# md_ver10_1.net
KiCad netlist of a schematic drawn in EAGLE
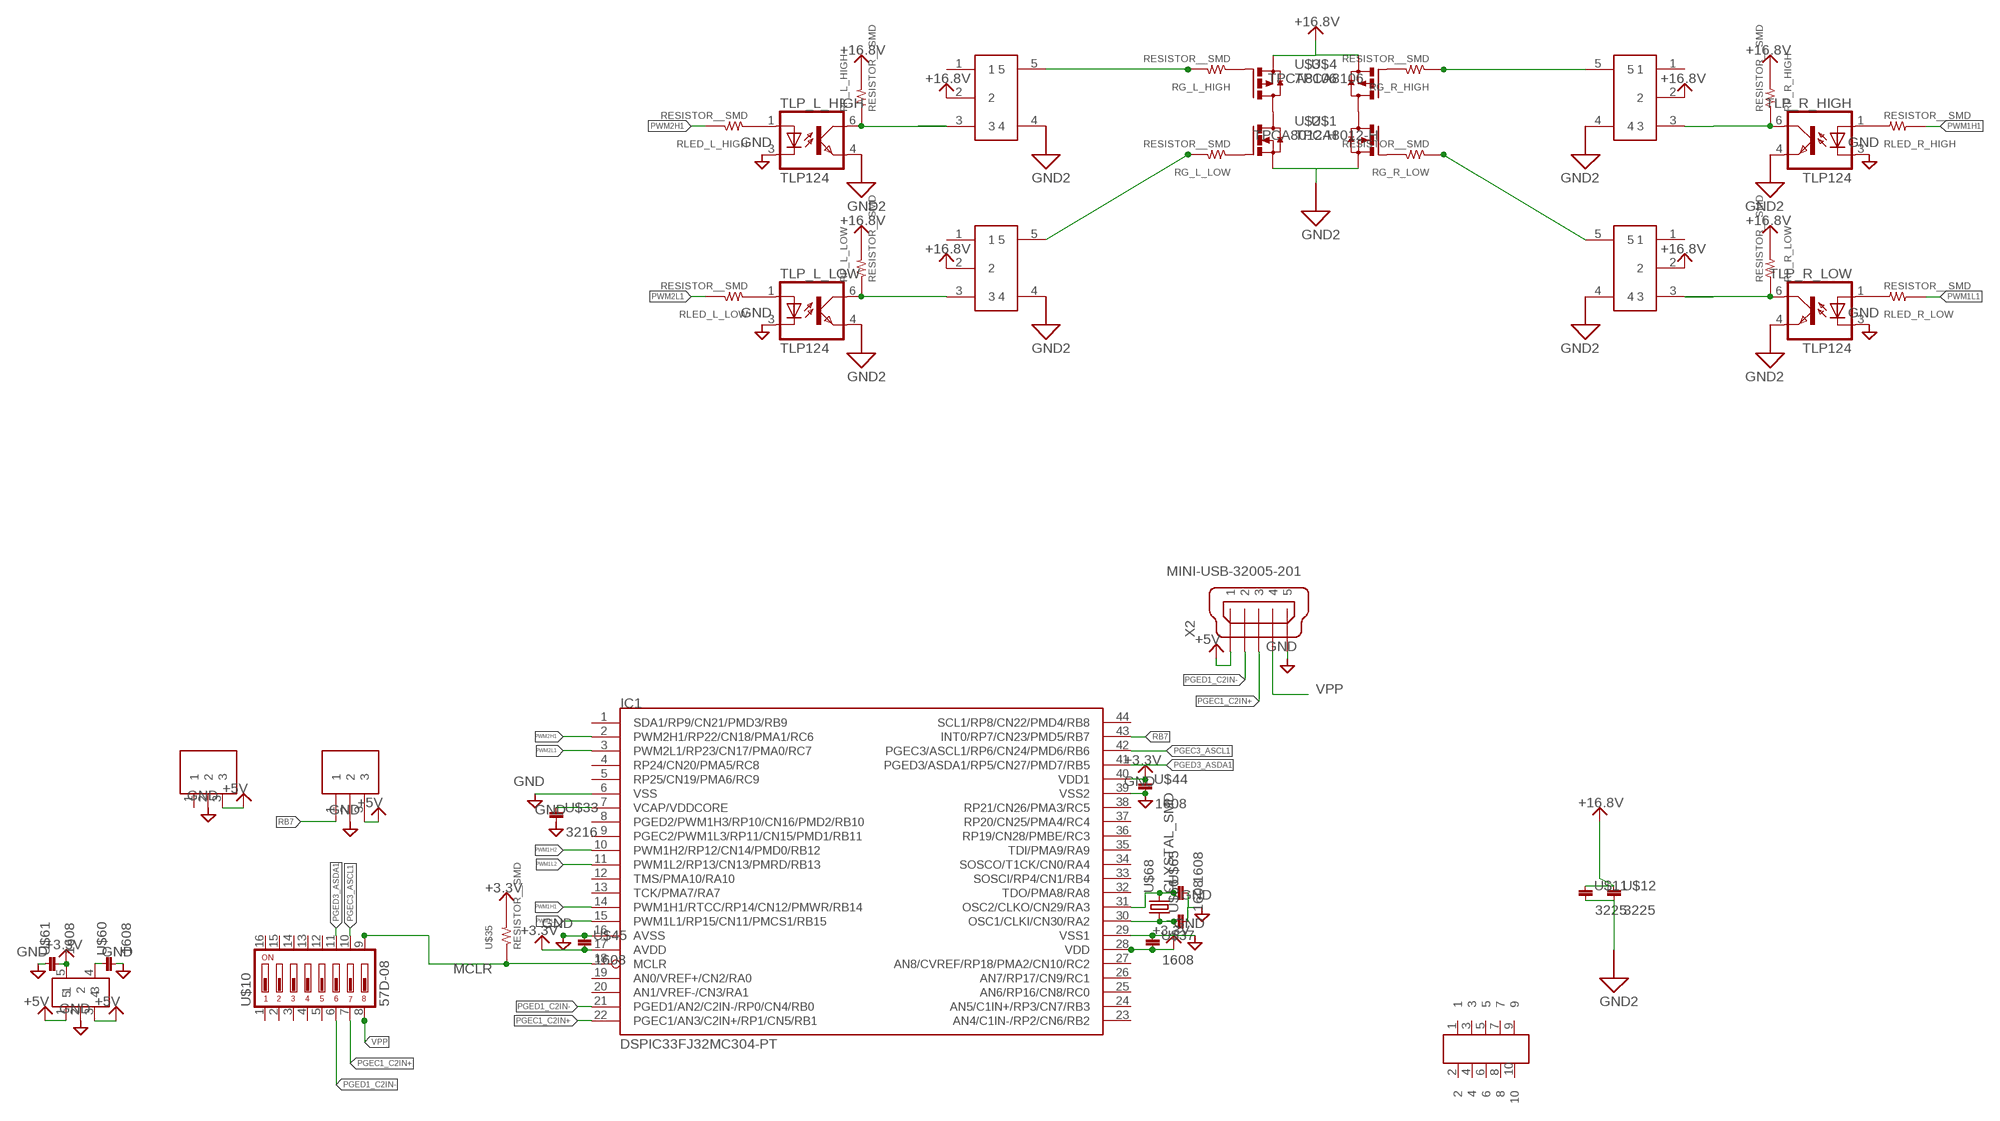
[diagram p0: schematic, sheet 1]

(export (version "E")
  (design (tool "Eeschema 10.0.6"))
  (components
    (comp (ref "IC1")
      (value "DSPIC33FJ32MC304-PT")
      (footprint "eagle-import:TQFP44")
      (libsource (lib "eagle-import") (part "DSPIC33FJ32MC304-PT"))
    )
    (comp (ref "IC_L_HIGH")
      (value "MCP1415")
      (footprint "eagle-import:SOT23-5L")
      (libsource (lib "eagle-import") (part "MCP1415"))
    )
    (comp (ref "IC_L_LOW")
      (value "MCP1415")
      (footprint "eagle-import:SOT23-5L")
      (libsource (lib "eagle-import") (part "MCP1415"))
    )
    (comp (ref "IC_R_HIGH")
      (value "MCP1415")
      (footprint "eagle-import:SOT23-5L")
      (libsource (lib "eagle-import") (part "MCP1415"))
    )
    (comp (ref "IC_R_LOW")
      (value "MCP1415")
      (footprint "eagle-import:SOT23-5L")
      (libsource (lib "eagle-import") (part "MCP1415"))
    )
    (comp (ref "RG_L_HIGH")
      (value "RESISTOR__SMD")
      (footprint "eagle-import:1608")
      (libsource (lib "eagle-import") (part "RESISTOR__SMD"))
    )
    (comp (ref "RG_L_LOW")
      (value "RESISTOR__SMD")
      (footprint "eagle-import:1608")
      (libsource (lib "eagle-import") (part "RESISTOR__SMD"))
    )
    (comp (ref "RG_R_HIGH")
      (value "RESISTOR__SMD")
      (footprint "eagle-import:1608")
      (libsource (lib "eagle-import") (part "RESISTOR__SMD"))
    )
    (comp (ref "RG_R_LOW")
      (value "RESISTOR__SMD")
      (footprint "eagle-import:1608")
      (libsource (lib "eagle-import") (part "RESISTOR__SMD"))
    )
    (comp (ref "RLED_L_HIGH")
      (value "RESISTOR__SMD")
      (footprint "eagle-import:1608")
      (libsource (lib "eagle-import") (part "RESISTOR__SMD"))
    )
    (comp (ref "RLED_L_LOW")
      (value "RESISTOR__SMD")
      (footprint "eagle-import:1608")
      (libsource (lib "eagle-import") (part "RESISTOR__SMD"))
    )
    (comp (ref "RLED_R_HIGH")
      (value "RESISTOR__SMD")
      (footprint "eagle-import:1608")
      (libsource (lib "eagle-import") (part "RESISTOR__SMD"))
    )
    (comp (ref "RLED_R_LOW")
      (value "RESISTOR__SMD")
      (footprint "eagle-import:1608")
      (libsource (lib "eagle-import") (part "RESISTOR__SMD"))
    )
    (comp (ref "RP_L_HIGH")
      (value "RESISTOR__SMD")
      (footprint "eagle-import:1608")
      (libsource (lib "eagle-import") (part "RESISTOR__SMD"))
    )
    (comp (ref "RP_L_LOW")
      (value "RESISTOR__SMD")
      (footprint "eagle-import:1608")
      (libsource (lib "eagle-import") (part "RESISTOR__SMD"))
    )
    (comp (ref "RP_R_HIGH")
      (value "RESISTOR__SMD")
      (footprint "eagle-import:1608")
      (libsource (lib "eagle-import") (part "RESISTOR__SMD"))
    )
    (comp (ref "RP_R_LOW")
      (value "RESISTOR__SMD")
      (footprint "eagle-import:1608")
      (libsource (lib "eagle-import") (part "RESISTOR__SMD"))
    )
    (comp (ref "TLP_L_HIGH")
      (value "TLP124")
      (footprint "eagle-import:11−4C1")
      (libsource (lib "eagle-import") (part "TLP124"))
    )
    (comp (ref "TLP_L_LOW")
      (value "TLP124")
      (footprint "eagle-import:11−4C1")
      (libsource (lib "eagle-import") (part "TLP124"))
    )
    (comp (ref "TLP_R_HIGH")
      (value "TLP124")
      (footprint "eagle-import:11−4C1")
      (libsource (lib "eagle-import") (part "TLP124"))
    )
    (comp (ref "TLP_R_LOW")
      (value "TLP124")
      (footprint "eagle-import:11−4C1")
      (libsource (lib "eagle-import") (part "TLP124"))
    )
    (comp (ref "U$1")
      (value "TPCA8012-H")
      (footprint "eagle-import:2-5Q1A")
      (libsource (lib "eagle-import") (part "TPCA8012-H"))
    )
    (comp (ref "U$2")
      (value "TPCA8012-H")
      (footprint "eagle-import:2-5Q1A")
      (libsource (lib "eagle-import") (part "TPCA8012-H"))
    )
    (comp (ref "U$3")
      (value "TPCA8106")
      (footprint "eagle-import:2-5Q1A")
      (libsource (lib "eagle-import") (part "TPCA8106"))
    )
    (comp (ref "U$4")
      (value "TPCA8106")
      (footprint "eagle-import:2-5Q1A")
      (libsource (lib "eagle-import") (part "TPCA8106"))
    )
    (comp (ref "U$7")
      (value "ＰＬ－ＩＲＭ")
      (footprint "eagle-import:ＰＬ－ＩＲＭ")
      (libsource (lib "eagle-import") (part "ＰＬ－ＩＲＭ"))
    )
    (comp (ref "U$8")
      (value "Ｒ－７８Ｅ５．０")
      (footprint "eagle-import:Ｒ－７８Ｅ５．０")
      (libsource (lib "eagle-import") (part "Ｒ－７８Ｅ５．０"))
    )
    (comp (ref "U$9")
      (value "TAR5SB")
      (footprint "eagle-import:SSOP5-P-0.95")
      (libsource (lib "eagle-import") (part "TAR5SB"))
    )
    (comp (ref "U$10")
      (value "57D-08")
      (footprint "eagle-import:57D")
      (libsource (lib "eagle-import") (part "57D-08"))
    )
    (comp (ref "U$11")
      (value "3225")
      (footprint "eagle-import:3225")
      (libsource (lib "eagle-import") (part "3225"))
    )
    (comp (ref "U$12")
      (value "3225")
      (footprint "eagle-import:3225")
      (libsource (lib "eagle-import") (part "3225"))
    )
    (comp (ref "U$15")
      (value "PIN_HEADER_52")
      (footprint "eagle-import:PIN_HEADER_5_2")
      (libsource (lib "eagle-import") (part "PIN_HEADER_52"))
    )
    (comp (ref "U$33")
      (value "3216")
      (footprint "eagle-import:3216")
      (libsource (lib "eagle-import") (part "3216"))
    )
    (comp (ref "U$35")
      (value "RESISTOR__SMD")
      (footprint "eagle-import:1608")
      (libsource (lib "eagle-import") (part "RESISTOR__SMD"))
    )
    (comp (ref "U$37")
      (value "1608")
      (footprint "eagle-import:1608")
      (libsource (lib "eagle-import") (part "1608"))
    )
    (comp (ref "U$44")
      (value "1608")
      (footprint "eagle-import:1608")
      (libsource (lib "eagle-import") (part "1608"))
    )
    (comp (ref "U$45")
      (value "1608")
      (footprint "eagle-import:1608")
      (libsource (lib "eagle-import") (part "1608"))
    )
    (comp (ref "U$60")
      (value "1608")
      (footprint "eagle-import:1608")
      (libsource (lib "eagle-import") (part "1608"))
    )
    (comp (ref "U$61")
      (value "1608")
      (footprint "eagle-import:1608")
      (libsource (lib "eagle-import") (part "1608"))
    )
    (comp (ref "U$65")
      (value "1608")
      (footprint "eagle-import:1608")
      (libsource (lib "eagle-import") (part "1608"))
    )
    (comp (ref "U$66")
      (value "1608")
      (footprint "eagle-import:1608")
      (libsource (lib "eagle-import") (part "1608"))
    )
    (comp (ref "U$68")
      (value "CLYSTAL_SMD")
      (footprint "eagle-import:CRYSTAL_SMD")
      (libsource (lib "eagle-import") (part "CLYSTAL_SMD"))
    )
    (comp (ref "X2")
      (value "MINI-USB-32005-201")
      (footprint "eagle-import:32005-201")
      (libsource (lib "eagle-import") (part "MINI-USB-32005-201"))
    )
  )
  (nets
    (net (code "1") (name "+3.3V") (class "Default")
      (node (ref "IC1") (pin "17") (pinfunction "AVDD_17") (pintype "power_in"))
      (node (ref "IC1") (pin "28") (pinfunction "VDD_28") (pintype "power_in"))
      (node (ref "IC1") (pin "40") (pinfunction "VDD1_40") (pintype "power_in"))
      (node (ref "U$35") (pin "2") (pinfunction "P$2_2") (pintype "passive"))
      (node (ref "U$37") (pin "P$2") (pinfunction "2_P$2") (pintype "passive"))
      (node (ref "U$44") (pin "P$1") (pinfunction "1_P$1") (pintype "passive"))
      (node (ref "U$45") (pin "P$2") (pinfunction "2_P$2") (pintype "passive"))
      (node (ref "U$61") (pin "P$2") (pinfunction "2_P$2") (pintype "passive"))
      (node (ref "U$9") (pin "5") (pinfunction "5_5") (pintype "bidirectional"))
    )
    (net (code "2") (name "+5V") (class "Default")
      (node (ref "U$7") (pin "3") (pinfunction "3_3") (pintype "bidirectional"))
      (node (ref "U$8") (pin "3") (pinfunction "3_3") (pintype "bidirectional"))
      (node (ref "U$9") (pin "1") (pinfunction "1_1") (pintype "bidirectional"))
      (node (ref "U$9") (pin "3") (pinfunction "3_3") (pintype "bidirectional"))
      (node (ref "X2") (pin "1") (pinfunction "1_1") (pintype "passive"))
    )
    (net (code "3") (name "+16.8V") (class "Default")
      (node (ref "IC_L_HIGH") (pin "2") (pinfunction "2_2") (pintype "bidirectional"))
      (node (ref "IC_L_LOW") (pin "2") (pinfunction "2_2") (pintype "bidirectional"))
      (node (ref "IC_R_HIGH") (pin "2") (pinfunction "2_2") (pintype "bidirectional"))
      (node (ref "IC_R_LOW") (pin "2") (pinfunction "2_2") (pintype "bidirectional"))
      (node (ref "RP_L_HIGH") (pin "2") (pinfunction "P$2_2") (pintype "passive"))
      (node (ref "RP_L_LOW") (pin "2") (pinfunction "P$2_2") (pintype "passive"))
      (node (ref "RP_R_HIGH") (pin "2") (pinfunction "P$2_2") (pintype "passive"))
      (node (ref "RP_R_LOW") (pin "2") (pinfunction "P$2_2") (pintype "passive"))
      (node (ref "U$11") (pin "P$1") (pinfunction "1_P$1") (pintype "passive"))
      (node (ref "U$12") (pin "P$1") (pinfunction "1_P$1") (pintype "passive"))
      (node (ref "U$3") (pin "1") (pinfunction "S_1") (pintype "passive"))
      (node (ref "U$3") (pin "2") (pinfunction "S_2") (pintype "passive"))
      (node (ref "U$3") (pin "3") (pinfunction "S_3") (pintype "passive"))
      (node (ref "U$4") (pin "1") (pinfunction "S_1") (pintype "passive"))
      (node (ref "U$4") (pin "2") (pinfunction "S_2") (pintype "passive"))
      (node (ref "U$4") (pin "3") (pinfunction "S_3") (pintype "passive"))
    )
    (net (code "4") (name "/MCLR") (class "Default")
      (node (ref "IC1") (pin "18") (pinfunction "MCLR_18") (pintype "input"))
      (node (ref "U$10") (pin "9") (pinfunction "9_9") (pintype "passive"))
      (node (ref "U$35") (pin "1") (pinfunction "P$1_1") (pintype "passive"))
    )
    (net (code "5") (name "GND") (class "Default")
      (node (ref "IC1") (pin "16") (pinfunction "AVSS_16") (pintype "power_in"))
      (node (ref "IC1") (pin "29") (pinfunction "VSS1_29") (pintype "power_in"))
      (node (ref "IC1") (pin "39") (pinfunction "VSS2_39") (pintype "power_in"))
      (node (ref "IC1") (pin "6") (pinfunction "VSS_6") (pintype "power_in"))
      (node (ref "TLP_L_HIGH") (pin "3") (pinfunction "C_3") (pintype "passive"))
      (node (ref "TLP_L_LOW") (pin "3") (pinfunction "C_3") (pintype "passive"))
      (node (ref "TLP_R_HIGH") (pin "3") (pinfunction "C_3") (pintype "passive"))
      (node (ref "TLP_R_LOW") (pin "3") (pinfunction "C_3") (pintype "passive"))
      (node (ref "U$33") (pin "P$2") (pinfunction "2_P$2") (pintype "passive"))
      (node (ref "U$37") (pin "P$1") (pinfunction "1_P$1") (pintype "passive"))
      (node (ref "U$44") (pin "P$2") (pinfunction "2_P$2") (pintype "passive"))
      (node (ref "U$45") (pin "P$1") (pinfunction "1_P$1") (pintype "passive"))
      (node (ref "U$60") (pin "P$2") (pinfunction "2_P$2") (pintype "passive"))
      (node (ref "U$61") (pin "P$1") (pinfunction "1_P$1") (pintype "passive"))
      (node (ref "U$65") (pin "P$2") (pinfunction "2_P$2") (pintype "passive"))
      (node (ref "U$66") (pin "P$2") (pinfunction "2_P$2") (pintype "passive"))
      (node (ref "U$7") (pin "2") (pinfunction "2_2") (pintype "bidirectional"))
      (node (ref "U$8") (pin "2") (pinfunction "2_2") (pintype "bidirectional"))
      (node (ref "U$9") (pin "2") (pinfunction "2_2") (pintype "bidirectional"))
      (node (ref "X2") (pin "5") (pinfunction "5_5") (pintype "passive"))
    )
    (net (code "6") (name "GND2") (class "Default")
      (node (ref "IC_L_HIGH") (pin "4") (pinfunction "4_4") (pintype "bidirectional"))
      (node (ref "IC_L_LOW") (pin "4") (pinfunction "4_4") (pintype "bidirectional"))
      (node (ref "IC_R_HIGH") (pin "4") (pinfunction "4_4") (pintype "bidirectional"))
      (node (ref "IC_R_LOW") (pin "4") (pinfunction "4_4") (pintype "bidirectional"))
      (node (ref "TLP_L_HIGH") (pin "4") (pinfunction "EMIT_4") (pintype "passive"))
      (node (ref "TLP_L_LOW") (pin "4") (pinfunction "EMIT_4") (pintype "passive"))
      (node (ref "TLP_R_HIGH") (pin "4") (pinfunction "EMIT_4") (pintype "passive"))
      (node (ref "TLP_R_LOW") (pin "4") (pinfunction "EMIT_4") (pintype "passive"))
      (node (ref "U$1") (pin "1") (pinfunction "S_1") (pintype "passive"))
      (node (ref "U$1") (pin "2") (pinfunction "S_2") (pintype "passive"))
      (node (ref "U$1") (pin "3") (pinfunction "S_3") (pintype "passive"))
      (node (ref "U$11") (pin "P$2") (pinfunction "2_P$2") (pintype "passive"))
      (node (ref "U$12") (pin "P$2") (pinfunction "2_P$2") (pintype "passive"))
      (node (ref "U$2") (pin "1") (pinfunction "S_1") (pintype "passive"))
      (node (ref "U$2") (pin "2") (pinfunction "S_2") (pintype "passive"))
      (node (ref "U$2") (pin "3") (pinfunction "S_3") (pintype "passive"))
    )
    (net (code "7") (name "Net-(IC1-OSC1{slash}CLKI{slash}CN30{slash}RA2)") (class "Default")
      (node (ref "IC1") (pin "30") (pinfunction "OSC1/CLKI/CN30/RA2_30") (pintype "bidirectional"))
      (node (ref "U$66") (pin "P$1") (pinfunction "1_P$1") (pintype "passive"))
      (node (ref "U$68") (pin "1") (pinfunction "1_1") (pintype "passive"))
    )
    (net (code "8") (name "Net-(IC1-OSC2{slash}CLKO{slash}CN29{slash}RA3)") (class "Default")
      (node (ref "IC1") (pin "31") (pinfunction "OSC2/CLKO/CN29/RA3_31") (pintype "bidirectional"))
      (node (ref "U$65") (pin "P$1") (pinfunction "1_P$1") (pintype "passive"))
      (node (ref "U$68") (pin "2") (pinfunction "2_2") (pintype "passive"))
    )
    (net (code "9") (name "Net-(IC1-VCAP{slash}VDDCORE)") (class "Default")
      (node (ref "IC1") (pin "7") (pinfunction "VCAP/VDDCORE_7") (pintype "power_in"))
      (node (ref "U$33") (pin "P$1") (pinfunction "1_P$1") (pintype "passive"))
    )
    (net (code "10") (name "Net-(RG_L_HIGH-P$1)") (class "Default")
      (node (ref "RG_L_HIGH") (pin "1") (pinfunction "P$1_1") (pintype "passive"))
      (node (ref "U$3") (pin "4") (pinfunction "G_4") (pintype "passive"))
    )
    (net (code "11") (name "Net-(RG_L_HIGH-P$2)") (class "Default")
      (node (ref "IC_L_HIGH") (pin "5") (pinfunction "5_5") (pintype "bidirectional"))
      (node (ref "RG_L_HIGH") (pin "2") (pinfunction "P$2_2") (pintype "passive"))
    )
    (net (code "12") (name "Net-(RG_L_LOW-P$1)") (class "Default")
      (node (ref "RG_L_LOW") (pin "1") (pinfunction "P$1_1") (pintype "passive"))
      (node (ref "U$2") (pin "4") (pinfunction "G_4") (pintype "passive"))
    )
    (net (code "13") (name "Net-(RG_L_LOW-P$2)") (class "Default")
      (node (ref "IC_L_LOW") (pin "5") (pinfunction "5_5") (pintype "bidirectional"))
      (node (ref "RG_L_LOW") (pin "2") (pinfunction "P$2_2") (pintype "passive"))
    )
    (net (code "14") (name "Net-(RG_R_HIGH-P$1)") (class "Default")
      (node (ref "IC_R_HIGH") (pin "5") (pinfunction "5_5") (pintype "bidirectional"))
      (node (ref "RG_R_HIGH") (pin "1") (pinfunction "P$1_1") (pintype "passive"))
    )
    (net (code "15") (name "Net-(RG_R_HIGH-P$2)") (class "Default")
      (node (ref "RG_R_HIGH") (pin "2") (pinfunction "P$2_2") (pintype "passive"))
      (node (ref "U$4") (pin "4") (pinfunction "G_4") (pintype "passive"))
    )
    (net (code "16") (name "Net-(RG_R_LOW-P$1)") (class "Default")
      (node (ref "IC_R_LOW") (pin "5") (pinfunction "5_5") (pintype "bidirectional"))
      (node (ref "RG_R_LOW") (pin "1") (pinfunction "P$1_1") (pintype "passive"))
    )
    (net (code "17") (name "Net-(RG_R_LOW-P$2)") (class "Default")
      (node (ref "RG_R_LOW") (pin "2") (pinfunction "P$2_2") (pintype "passive"))
      (node (ref "U$1") (pin "4") (pinfunction "G_4") (pintype "passive"))
    )
    (net (code "18") (name "Net-(RLED_L_HIGH-P$1)") (class "Default")
      (node (ref "RLED_L_HIGH") (pin "1") (pinfunction "P$1_1") (pintype "passive"))
      (node (ref "TLP_L_HIGH") (pin "1") (pinfunction "A_1") (pintype "passive"))
    )
    (net (code "19") (name "Net-(RLED_L_LOW-P$1)") (class "Default")
      (node (ref "RLED_L_LOW") (pin "1") (pinfunction "P$1_1") (pintype "passive"))
      (node (ref "TLP_L_LOW") (pin "1") (pinfunction "A_1") (pintype "passive"))
    )
    (net (code "20") (name "Net-(RLED_R_HIGH-P$1)") (class "Default")
      (node (ref "RLED_R_HIGH") (pin "1") (pinfunction "P$1_1") (pintype "passive"))
      (node (ref "TLP_R_HIGH") (pin "1") (pinfunction "A_1") (pintype "passive"))
    )
    (net (code "21") (name "Net-(RLED_R_LOW-P$1)") (class "Default")
      (node (ref "RLED_R_LOW") (pin "1") (pinfunction "P$1_1") (pintype "passive"))
      (node (ref "TLP_R_LOW") (pin "1") (pinfunction "A_1") (pintype "passive"))
    )
    (net (code "22") (name "Net-(RP_L_HIGH-P$1)") (class "Default")
      (node (ref "IC_L_HIGH") (pin "3") (pinfunction "3_3") (pintype "bidirectional"))
      (node (ref "RP_L_HIGH") (pin "1") (pinfunction "P$1_1") (pintype "passive"))
      (node (ref "TLP_L_HIGH") (pin "6") (pinfunction "COL_6") (pintype "passive"))
    )
    (net (code "23") (name "Net-(RP_L_LOW-P$1)") (class "Default")
      (node (ref "IC_L_LOW") (pin "3") (pinfunction "3_3") (pintype "bidirectional"))
      (node (ref "RP_L_LOW") (pin "1") (pinfunction "P$1_1") (pintype "passive"))
      (node (ref "TLP_L_LOW") (pin "6") (pinfunction "COL_6") (pintype "passive"))
    )
    (net (code "24") (name "Net-(RP_R_HIGH-P$1)") (class "Default")
      (node (ref "IC_R_HIGH") (pin "3") (pinfunction "3_3") (pintype "bidirectional"))
      (node (ref "RP_R_HIGH") (pin "1") (pinfunction "P$1_1") (pintype "passive"))
      (node (ref "TLP_R_HIGH") (pin "6") (pinfunction "COL_6") (pintype "passive"))
    )
    (net (code "25") (name "Net-(RP_R_LOW-P$1)") (class "Default")
      (node (ref "IC_R_LOW") (pin "3") (pinfunction "3_3") (pintype "bidirectional"))
      (node (ref "RP_R_LOW") (pin "1") (pinfunction "P$1_1") (pintype "passive"))
      (node (ref "TLP_R_LOW") (pin "6") (pinfunction "COL_6") (pintype "passive"))
    )
    (net (code "26") (name "Net-(U$1-D-Pad5)") (class "Default")
      (node (ref "U$1") (pin "5") (pinfunction "D_5") (pintype "passive"))
      (node (ref "U$1") (pin "6") (pinfunction "D_6") (pintype "passive"))
      (node (ref "U$1") (pin "7") (pinfunction "D_7") (pintype "passive"))
      (node (ref "U$1") (pin "8") (pinfunction "D_8") (pintype "passive"))
      (node (ref "U$4") (pin "5") (pinfunction "D_5") (pintype "passive"))
      (node (ref "U$4") (pin "6") (pinfunction "D_6") (pintype "passive"))
      (node (ref "U$4") (pin "7") (pinfunction "D_7") (pintype "passive"))
      (node (ref "U$4") (pin "8") (pinfunction "D_8") (pintype "passive"))
    )
    (net (code "27") (name "Net-(U$2-D-Pad5)") (class "Default")
      (node (ref "U$2") (pin "5") (pinfunction "D_5") (pintype "passive"))
      (node (ref "U$2") (pin "6") (pinfunction "D_6") (pintype "passive"))
      (node (ref "U$2") (pin "7") (pinfunction "D_7") (pintype "passive"))
      (node (ref "U$2") (pin "8") (pinfunction "D_8") (pintype "passive"))
      (node (ref "U$3") (pin "5") (pinfunction "D_5") (pintype "passive"))
      (node (ref "U$3") (pin "6") (pinfunction "D_6") (pintype "passive"))
      (node (ref "U$3") (pin "7") (pinfunction "D_7") (pintype "passive"))
      (node (ref "U$3") (pin "8") (pinfunction "D_8") (pintype "passive"))
    )
    (net (code "28") (name "Net-(U$60-1)") (class "Default")
      (node (ref "U$60") (pin "P$1") (pinfunction "1_P$1") (pintype "passive"))
      (node (ref "U$9") (pin "4") (pinfunction "4_4") (pintype "bidirectional"))
    )
    (net (code "29") (name "PGEC1_C2IN+") (class "Default")
      (node (ref "IC1") (pin "22") (pinfunction "PGEC1/AN3/C2IN+/RP1/CN5/RB1_22") (pintype "bidirectional"))
      (node (ref "U$10") (pin "7") (pinfunction "7_7") (pintype "passive"))
      (node (ref "X2") (pin "3") (pinfunction "3_3") (pintype "passive"))
    )
    (net (code "30") (name "PGEC3_ASCL1") (class "Default")
      (node (ref "IC1") (pin "42") (pinfunction "PGEC3/ASCL1/RP6/CN24/PMD6/RB6_42") (pintype "bidirectional"))
      (node (ref "U$10") (pin "10") (pinfunction "10_10") (pintype "passive"))
    )
    (net (code "31") (name "PGED1_C2IN-") (class "Default")
      (node (ref "IC1") (pin "21") (pinfunction "PGED1/AN2/C2IN-/RP0/CN4/RB0_21") (pintype "bidirectional"))
      (node (ref "U$10") (pin "6") (pinfunction "6_6") (pintype "passive"))
      (node (ref "X2") (pin "2") (pinfunction "2_2") (pintype "passive"))
    )
    (net (code "32") (name "PGED3_ASDA1") (class "Default")
      (node (ref "IC1") (pin "41") (pinfunction "PGED3/ASDA1/RP5/CN27/PMD7/RB5_41") (pintype "bidirectional"))
      (node (ref "U$10") (pin "11") (pinfunction "11_11") (pintype "passive"))
    )
    (net (code "33") (name "PWM1H1") (class "Default")
      (node (ref "IC1") (pin "14") (pinfunction "PWM1H1/RTCC/RP14/CN12/PMWR/RB14_14") (pintype "bidirectional"))
      (node (ref "RLED_R_HIGH") (pin "2") (pinfunction "P$2_2") (pintype "passive"))
    )
    (net (code "34") (name "PWM1H2") (class "Default")
      (node (ref "IC1") (pin "10") (pinfunction "PWM1H2/RP12/CN14/PMD0/RB12_10") (pintype "bidirectional"))
    )
    (net (code "35") (name "PWM1L1") (class "Default")
      (node (ref "IC1") (pin "15") (pinfunction "PWM1L1/RP15/CN11/PMCS1/RB15_15") (pintype "bidirectional"))
      (node (ref "RLED_R_LOW") (pin "2") (pinfunction "P$2_2") (pintype "passive"))
    )
    (net (code "36") (name "PWM1L2") (class "Default")
      (node (ref "IC1") (pin "11") (pinfunction "PWM1L2/RP13/CN13/PMRD/RB13_11") (pintype "bidirectional"))
    )
    (net (code "37") (name "PWM2H1") (class "Default")
      (node (ref "IC1") (pin "2") (pinfunction "PWM2H1/RP22/CN18/PMA1/RC6_2") (pintype "bidirectional"))
      (node (ref "RLED_L_HIGH") (pin "2") (pinfunction "P$2_2") (pintype "passive"))
    )
    (net (code "38") (name "PWM2L1") (class "Default")
      (node (ref "IC1") (pin "3") (pinfunction "PWM2L1/RP23/CN17/PMA0/RC7_3") (pintype "bidirectional"))
      (node (ref "RLED_L_LOW") (pin "2") (pinfunction "P$2_2") (pintype "passive"))
    )
    (net (code "39") (name "RB7") (class "Default")
      (node (ref "IC1") (pin "43") (pinfunction "INT0/RP7/CN23/PMD5/RB7_43") (pintype "bidirectional"))
      (node (ref "U$7") (pin "1") (pinfunction "1_1") (pintype "bidirectional"))
    )
    (net (code "40") (name "VPP") (class "Default")
      (node (ref "U$10") (pin "8") (pinfunction "8_8") (pintype "passive"))
      (node (ref "X2") (pin "4") (pinfunction "4_4") (pintype "passive"))
    )
    (net (code "41") (name "unconnected-(IC1-AN0{slash}VREF+{slash}CN2{slash}RA0-Pad19)") (class "Default")
      (node (ref "IC1") (pin "19") (pinfunction "AN0/VREF+/CN2/RA0_19") (pintype "bidirectional"))
    )
    (net (code "42") (name "unconnected-(IC1-AN1{slash}VREF-{slash}CN3{slash}RA1-Pad20)") (class "Default")
      (node (ref "IC1") (pin "20") (pinfunction "AN1/VREF-/CN3/RA1_20") (pintype "bidirectional"))
    )
    (net (code "43") (name "unconnected-(IC1-AN4{slash}C1IN-{slash}RP2{slash}CN6{slash}RB2-Pad23)") (class "Default")
      (node (ref "IC1") (pin "23") (pinfunction "AN4/C1IN-/RP2/CN6/RB2_23") (pintype "bidirectional"))
    )
    (net (code "44") (name "unconnected-(IC1-AN5{slash}C1IN+{slash}RP3{slash}CN7{slash}RB3-Pad24)") (class "Default")
      (node (ref "IC1") (pin "24") (pinfunction "AN5/C1IN+/RP3/CN7/RB3_24") (pintype "bidirectional"))
    )
    (net (code "45") (name "unconnected-(IC1-AN6{slash}RP16{slash}CN8{slash}RC0-Pad25)") (class "Default")
      (node (ref "IC1") (pin "25") (pinfunction "AN6/RP16/CN8/RC0_25") (pintype "bidirectional"))
    )
    (net (code "46") (name "unconnected-(IC1-AN7{slash}RP17{slash}CN9{slash}RC1-Pad26)") (class "Default")
      (node (ref "IC1") (pin "26") (pinfunction "AN7/RP17/CN9/RC1_26") (pintype "bidirectional"))
    )
    (net (code "47") (name "unconnected-(IC1-AN8{slash}CVREF{slash}RP18{slash}PMA2{slash}CN10{slash}RC2-Pad27)") (class "Default")
      (node (ref "IC1") (pin "27") (pinfunction "AN8/CVREF/RP18/PMA2/CN10/RC2_27") (pintype "bidirectional"))
    )
    (net (code "48") (name "unconnected-(IC1-PGEC2{slash}PWM1L3{slash}RP11{slash}CN15{slash}PMD1{slash}RB11-Pad9)") (class "Default")
      (node (ref "IC1") (pin "9") (pinfunction "PGEC2/PWM1L3/RP11/CN15/PMD1/RB11_9") (pintype "bidirectional"))
    )
    (net (code "49") (name "unconnected-(IC1-PGED2{slash}PWM1H3{slash}RP10{slash}CN16{slash}PMD2{slash}RB10-Pad8)") (class "Default")
      (node (ref "IC1") (pin "8") (pinfunction "PGED2/PWM1H3/RP10/CN16/PMD2/RB10_8") (pintype "bidirectional"))
    )
    (net (code "50") (name "unconnected-(IC1-RP19{slash}CN28{slash}PMBE{slash}RC3-Pad36)") (class "Default")
      (node (ref "IC1") (pin "36") (pinfunction "RP19/CN28/PMBE/RC3_36") (pintype "bidirectional"))
    )
    (net (code "51") (name "unconnected-(IC1-RP20{slash}CN25{slash}PMA4{slash}RC4-Pad37)") (class "Default")
      (node (ref "IC1") (pin "37") (pinfunction "RP20/CN25/PMA4/RC4_37") (pintype "bidirectional"))
    )
    (net (code "52") (name "unconnected-(IC1-RP21{slash}CN26{slash}PMA3{slash}RC5-Pad38)") (class "Default")
      (node (ref "IC1") (pin "38") (pinfunction "RP21/CN26/PMA3/RC5_38") (pintype "bidirectional"))
    )
    (net (code "53") (name "unconnected-(IC1-RP24{slash}CN20{slash}PMA5{slash}RC8-Pad4)") (class "Default")
      (node (ref "IC1") (pin "4") (pinfunction "RP24/CN20/PMA5/RC8_4") (pintype "bidirectional"))
    )
    (net (code "54") (name "unconnected-(IC1-RP25{slash}CN19{slash}PMA6{slash}RC9-Pad5)") (class "Default")
      (node (ref "IC1") (pin "5") (pinfunction "RP25/CN19/PMA6/RC9_5") (pintype "bidirectional"))
    )
    (net (code "55") (name "unconnected-(IC1-SCL1{slash}RP8{slash}CN22{slash}PMD4{slash}RB8-Pad44)") (class "Default")
      (node (ref "IC1") (pin "44") (pinfunction "SCL1/RP8/CN22/PMD4/RB8_44") (pintype "bidirectional"))
    )
    (net (code "56") (name "unconnected-(IC1-SDA1{slash}RP9{slash}CN21{slash}PMD3{slash}RB9-Pad1)") (class "Default")
      (node (ref "IC1") (pin "1") (pinfunction "SDA1/RP9/CN21/PMD3/RB9_1") (pintype "bidirectional"))
    )
    (net (code "57") (name "unconnected-(IC1-SOSCI{slash}RP4{slash}CN1{slash}RB4-Pad33)") (class "Default")
      (node (ref "IC1") (pin "33") (pinfunction "SOSCI/RP4/CN1/RB4_33") (pintype "bidirectional"))
    )
    (net (code "58") (name "unconnected-(IC1-SOSCO{slash}T1CK{slash}CN0{slash}RA4-Pad34)") (class "Default")
      (node (ref "IC1") (pin "34") (pinfunction "SOSCO/T1CK/CN0/RA4_34") (pintype "bidirectional"))
    )
    (net (code "59") (name "unconnected-(IC1-TCK{slash}PMA7{slash}RA7-Pad13)") (class "Default")
      (node (ref "IC1") (pin "13") (pinfunction "TCK/PMA7/RA7_13") (pintype "bidirectional"))
    )
    (net (code "60") (name "unconnected-(IC1-TDI{slash}PMA9{slash}RA9-Pad35)") (class "Default")
      (node (ref "IC1") (pin "35") (pinfunction "TDI/PMA9/RA9_35") (pintype "bidirectional"))
    )
    (net (code "61") (name "unconnected-(IC1-TDO{slash}PMA8{slash}RA8-Pad32)") (class "Default")
      (node (ref "IC1") (pin "32") (pinfunction "TDO/PMA8/RA8_32") (pintype "bidirectional"))
    )
    (net (code "62") (name "unconnected-(IC1-TMS{slash}PMA10{slash}RA10-Pad12)") (class "Default")
      (node (ref "IC1") (pin "12") (pinfunction "TMS/PMA10/RA10_12") (pintype "bidirectional"))
    )
    (net (code "63") (name "unconnected-(IC_L_HIGH-Pad1)") (class "Default")
      (node (ref "IC_L_HIGH") (pin "1") (pinfunction "1_1") (pintype "bidirectional"))
    )
    (net (code "64") (name "unconnected-(IC_L_LOW-Pad1)") (class "Default")
      (node (ref "IC_L_LOW") (pin "1") (pinfunction "1_1") (pintype "bidirectional"))
    )
    (net (code "65") (name "unconnected-(IC_R_HIGH-Pad1)") (class "Default")
      (node (ref "IC_R_HIGH") (pin "1") (pinfunction "1_1") (pintype "bidirectional"))
    )
    (net (code "66") (name "unconnected-(IC_R_LOW-Pad1)") (class "Default")
      (node (ref "IC_R_LOW") (pin "1") (pinfunction "1_1") (pintype "bidirectional"))
    )
    (net (code "67") (name "unconnected-(U$8-Pad1)") (class "Default")
      (node (ref "U$8") (pin "1") (pinfunction "1_1") (pintype "bidirectional"))
    )
    (net (code "68") (name "unconnected-(U$10-Pad1)") (class "Default")
      (node (ref "U$10") (pin "1") (pinfunction "1_1") (pintype "passive"))
    )
    (net (code "69") (name "unconnected-(U$10-Pad2)") (class "Default")
      (node (ref "U$10") (pin "2") (pinfunction "2_2") (pintype "passive"))
    )
    (net (code "70") (name "unconnected-(U$10-Pad3)") (class "Default")
      (node (ref "U$10") (pin "3") (pinfunction "3_3") (pintype "passive"))
    )
    (net (code "71") (name "unconnected-(U$10-Pad4)") (class "Default")
      (node (ref "U$10") (pin "4") (pinfunction "4_4") (pintype "passive"))
    )
    (net (code "72") (name "unconnected-(U$10-Pad5)") (class "Default")
      (node (ref "U$10") (pin "5") (pinfunction "5_5") (pintype "passive"))
    )
    (net (code "73") (name "unconnected-(U$10-Pad12)") (class "Default")
      (node (ref "U$10") (pin "12") (pinfunction "12_12") (pintype "passive"))
    )
    (net (code "74") (name "unconnected-(U$10-Pad13)") (class "Default")
      (node (ref "U$10") (pin "13") (pinfunction "13_13") (pintype "passive"))
    )
    (net (code "75") (name "unconnected-(U$10-Pad14)") (class "Default")
      (node (ref "U$10") (pin "14") (pinfunction "14_14") (pintype "passive"))
    )
    (net (code "76") (name "unconnected-(U$10-Pad15)") (class "Default")
      (node (ref "U$10") (pin "15") (pinfunction "15_15") (pintype "passive"))
    )
    (net (code "77") (name "unconnected-(U$10-Pad16)") (class "Default")
      (node (ref "U$10") (pin "16") (pinfunction "16_16") (pintype "passive"))
    )
    (net (code "78") (name "unconnected-(U$15-Pad1)") (class "Default")
      (node (ref "U$15") (pin "1") (pinfunction "1_1") (pintype "bidirectional"))
    )
    (net (code "79") (name "unconnected-(U$15-Pad2)") (class "Default")
      (node (ref "U$15") (pin "2") (pinfunction "2_2") (pintype "bidirectional"))
    )
    (net (code "80") (name "unconnected-(U$15-Pad3)") (class "Default")
      (node (ref "U$15") (pin "3") (pinfunction "3_3") (pintype "bidirectional"))
    )
    (net (code "81") (name "unconnected-(U$15-Pad4)") (class "Default")
      (node (ref "U$15") (pin "4") (pinfunction "4_4") (pintype "bidirectional"))
    )
    (net (code "82") (name "unconnected-(U$15-Pad5)") (class "Default")
      (node (ref "U$15") (pin "5") (pinfunction "5_5") (pintype "bidirectional"))
    )
    (net (code "83") (name "unconnected-(U$15-Pad6)") (class "Default")
      (node (ref "U$15") (pin "6") (pinfunction "6_6") (pintype "bidirectional"))
    )
    (net (code "84") (name "unconnected-(U$15-Pad7)") (class "Default")
      (node (ref "U$15") (pin "7") (pinfunction "7_7") (pintype "bidirectional"))
    )
    (net (code "85") (name "unconnected-(U$15-Pad8)") (class "Default")
      (node (ref "U$15") (pin "8") (pinfunction "8_8") (pintype "bidirectional"))
    )
    (net (code "86") (name "unconnected-(U$15-Pad9)") (class "Default")
      (node (ref "U$15") (pin "9") (pinfunction "9_9") (pintype "bidirectional"))
    )
    (net (code "87") (name "unconnected-(U$15-Pad10)") (class "Default")
      (node (ref "U$15") (pin "10") (pinfunction "10_10") (pintype "bidirectional"))
    )
  )
)
